# v2164_quad_VCA_0402.net
KiCad netlist of a schematic drawn in EAGLE
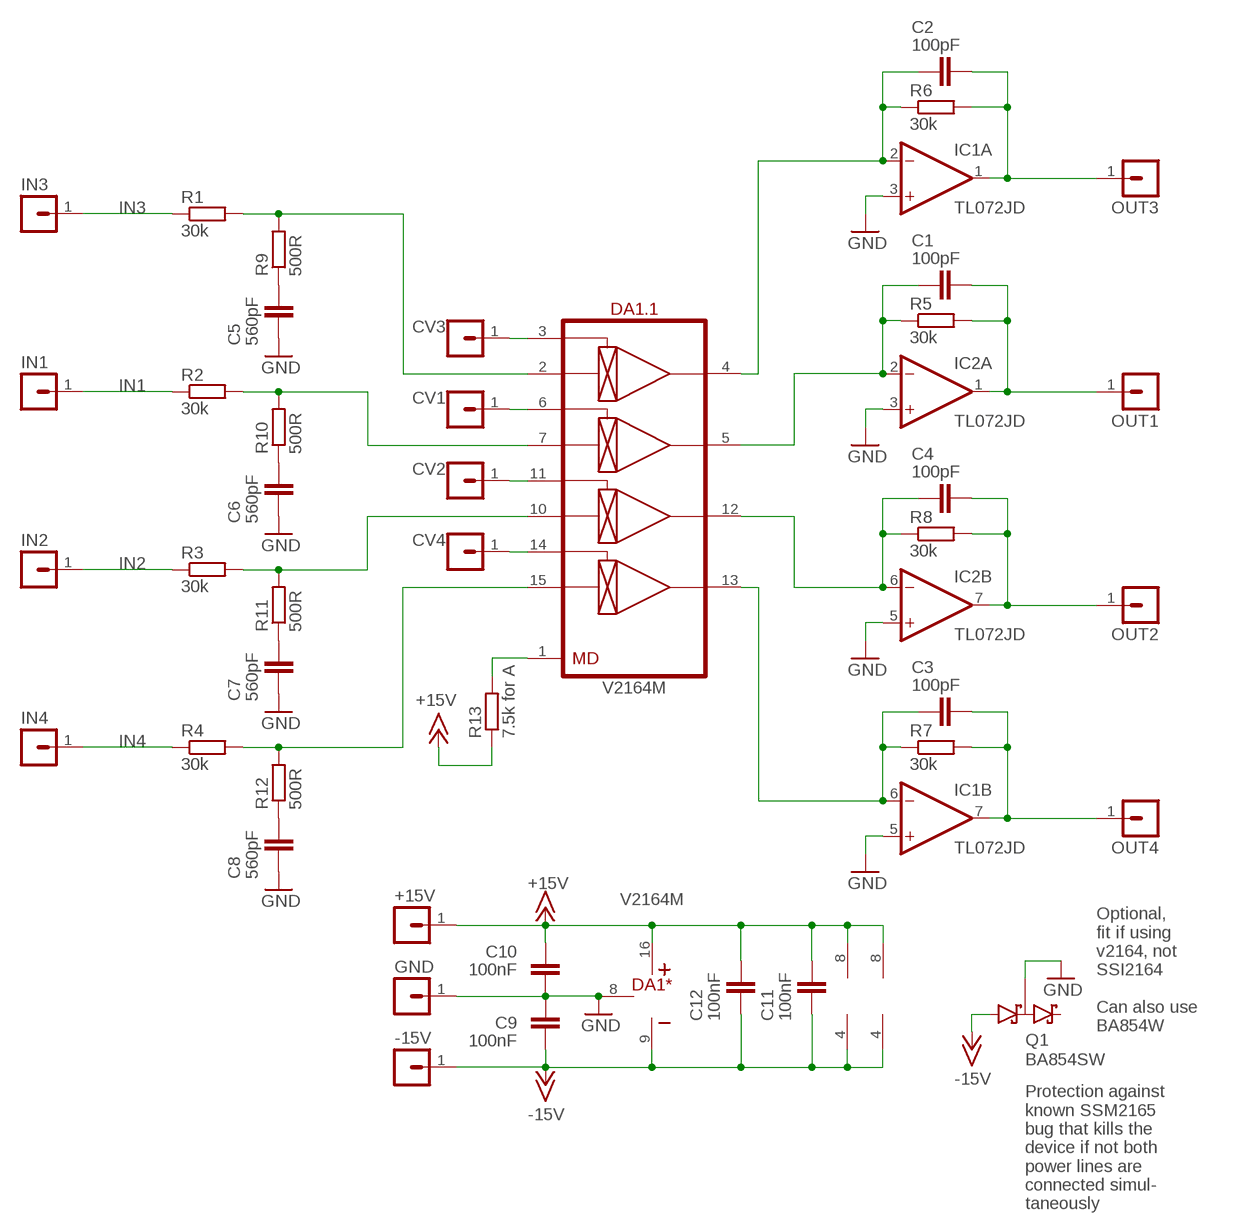
[diagram p0: schematic, sheet 1]

(export (version "E")
  (design (tool "Eeschema 10.0.6"))
  (components
    (comp (ref "+15V")
      (value "MA01-1JN")
      (footprint "eagle-import:MA01N-1J")
      (libsource (lib "eagle-import") (part "MA01-1JN"))
    )
    (comp (ref "-15V")
      (value "MA01-1JN")
      (footprint "eagle-import:MA01N-1J")
      (libsource (lib "eagle-import") (part "MA01-1JN"))
    )
    (comp (ref "C1")
      (value "100pF")
      (footprint "eagle-import:C0402")
      (libsource (lib "eagle-import") (part "C-EUC0402"))
    )
    (comp (ref "C2")
      (value "100pF")
      (footprint "eagle-import:C0402")
      (libsource (lib "eagle-import") (part "C-EUC0402"))
    )
    (comp (ref "C3")
      (value "100pF")
      (footprint "eagle-import:C0402")
      (libsource (lib "eagle-import") (part "C-EUC0402"))
    )
    (comp (ref "C4")
      (value "100pF")
      (footprint "eagle-import:C0402")
      (libsource (lib "eagle-import") (part "C-EUC0402"))
    )
    (comp (ref "C5")
      (value "560pF")
      (footprint "eagle-import:C0603")
      (libsource (lib "eagle-import") (part "C-EUC0603"))
    )
    (comp (ref "C6")
      (value "560pF")
      (footprint "eagle-import:C0603")
      (libsource (lib "eagle-import") (part "C-EUC0603"))
    )
    (comp (ref "C7")
      (value "560pF")
      (footprint "eagle-import:C0603")
      (libsource (lib "eagle-import") (part "C-EUC0603"))
    )
    (comp (ref "C8")
      (value "560pF")
      (footprint "eagle-import:C0603")
      (libsource (lib "eagle-import") (part "C-EUC0603"))
    )
    (comp (ref "C9")
      (value "100nF")
      (footprint "eagle-import:C0402")
      (libsource (lib "eagle-import") (part "C-EUC0402"))
    )
    (comp (ref "C10")
      (value "100nF")
      (footprint "eagle-import:C0402")
      (libsource (lib "eagle-import") (part "C-EUC0402"))
    )
    (comp (ref "C11")
      (value "100nF")
      (footprint "eagle-import:C0402")
      (libsource (lib "eagle-import") (part "C-EUC0402"))
    )
    (comp (ref "C12")
      (value "100nF")
      (footprint "eagle-import:C0402")
      (libsource (lib "eagle-import") (part "C-EUC0402"))
    )
    (comp (ref "CV1")
      (value "MA01-1JN")
      (footprint "eagle-import:MA01N-1J")
      (libsource (lib "eagle-import") (part "MA01-1JN"))
    )
    (comp (ref "CV2")
      (value "MA01-1JN")
      (footprint "eagle-import:MA01N-1J")
      (libsource (lib "eagle-import") (part "MA01-1JN"))
    )
    (comp (ref "CV3")
      (value "MA01-1JN")
      (footprint "eagle-import:MA01N-1J")
      (libsource (lib "eagle-import") (part "MA01-1JN"))
    )
    (comp (ref "CV4")
      (value "MA01-1JN")
      (footprint "eagle-import:MA01N-1J")
      (libsource (lib "eagle-import") (part "MA01-1JN"))
    )
    (comp (ref "DA1")
      (value "V2164M")
      (footprint "eagle-import:SO-16")
      (libsource (lib "eagle-import") (part "V2164M"))
    )
    (comp (ref "GND")
      (value "MA01-1JN")
      (footprint "eagle-import:MA01N-1J")
      (libsource (lib "eagle-import") (part "MA01-1JN"))
    )
    (comp (ref "IC1")
      (value "TL072JD")
      (footprint "eagle-import:SO08J")
      (libsource (lib "eagle-import") (part "TL072JD"))
    )
    (comp (ref "IC2")
      (value "TL072JD")
      (footprint "eagle-import:SO08J")
      (libsource (lib "eagle-import") (part "TL072JD"))
    )
    (comp (ref "IN1")
      (value "MA01-1JN")
      (footprint "eagle-import:MA01N-1J")
      (libsource (lib "eagle-import") (part "MA01-1JN"))
    )
    (comp (ref "IN2")
      (value "MA01-1JN")
      (footprint "eagle-import:MA01N-1J")
      (libsource (lib "eagle-import") (part "MA01-1JN"))
    )
    (comp (ref "IN3")
      (value "MA01-1JN")
      (footprint "eagle-import:MA01N-1J")
      (libsource (lib "eagle-import") (part "MA01-1JN"))
    )
    (comp (ref "IN4")
      (value "MA01-1JN")
      (footprint "eagle-import:MA01N-1J")
      (libsource (lib "eagle-import") (part "MA01-1JN"))
    )
    (comp (ref "OUT1")
      (value "MA01-1JN")
      (footprint "eagle-import:MA01N-1J")
      (libsource (lib "eagle-import") (part "MA01-1JN"))
    )
    (comp (ref "OUT2")
      (value "MA01-1JN")
      (footprint "eagle-import:MA01N-1J")
      (libsource (lib "eagle-import") (part "MA01-1JN"))
    )
    (comp (ref "OUT3")
      (value "MA01-1JN")
      (footprint "eagle-import:MA01N-1J")
      (libsource (lib "eagle-import") (part "MA01-1JN"))
    )
    (comp (ref "OUT4")
      (value "MA01-1JN")
      (footprint "eagle-import:MA01N-1J")
      (libsource (lib "eagle-import") (part "MA01-1JN"))
    )
    (comp (ref "Q1")
      (value "BA854SW")
      (footprint "eagle-import:SOT23-3J")
      (libsource (lib "eagle-import") (part "BA854SW"))
    )
    (comp (ref "R1")
      (value "30k")
      (footprint "eagle-import:R0402")
      (libsource (lib "eagle-import") (part "R-EU_R0402"))
    )
    (comp (ref "R2")
      (value "30k")
      (footprint "eagle-import:R0402")
      (libsource (lib "eagle-import") (part "R-EU_R0402"))
    )
    (comp (ref "R3")
      (value "30k")
      (footprint "eagle-import:R0402")
      (libsource (lib "eagle-import") (part "R-EU_R0402"))
    )
    (comp (ref "R4")
      (value "30k")
      (footprint "eagle-import:R0402")
      (libsource (lib "eagle-import") (part "R-EU_R0402"))
    )
    (comp (ref "R5")
      (value "30k")
      (footprint "eagle-import:R0402")
      (libsource (lib "eagle-import") (part "R-EU_R0402"))
    )
    (comp (ref "R6")
      (value "30k")
      (footprint "eagle-import:R0402")
      (libsource (lib "eagle-import") (part "R-EU_R0402"))
    )
    (comp (ref "R7")
      (value "30k")
      (footprint "eagle-import:R0402")
      (libsource (lib "eagle-import") (part "R-EU_R0402"))
    )
    (comp (ref "R8")
      (value "30k")
      (footprint "eagle-import:R0402")
      (libsource (lib "eagle-import") (part "R-EU_R0402"))
    )
    (comp (ref "R9")
      (value "500R")
      (footprint "eagle-import:R0402")
      (libsource (lib "eagle-import") (part "R-EU_R0402"))
    )
    (comp (ref "R10")
      (value "500R")
      (footprint "eagle-import:R0402")
      (libsource (lib "eagle-import") (part "R-EU_R0402"))
    )
    (comp (ref "R11")
      (value "500R")
      (footprint "eagle-import:R0402")
      (libsource (lib "eagle-import") (part "R-EU_R0402"))
    )
    (comp (ref "R12")
      (value "500R")
      (footprint "eagle-import:R0402")
      (libsource (lib "eagle-import") (part "R-EU_R0402"))
    )
    (comp (ref "R13")
      (value "7.5k for A")
      (footprint "eagle-import:R0402")
      (libsource (lib "eagle-import") (part "R-EU_R0402"))
    )
  )
  (nets
    (net (code "1") (name "+15V") (class "Default")
      (node (ref "+15V") (pin "1") (pinfunction "1_1") (pintype "passive"))
      (node (ref "C10") (pin "2") (pinfunction "2_2") (pintype "passive"))
      (node (ref "C11") (pin "2") (pinfunction "2_2") (pintype "passive"))
      (node (ref "C12") (pin "2") (pinfunction "2_2") (pintype "passive"))
      (node (ref "DA1") (pin "16") (pinfunction "V+_16") (pintype "power_in"))
      (node (ref "IC1") (pin "8") (pinfunction "V+_8") (pintype "power_in"))
      (node (ref "IC2") (pin "8") (pinfunction "V+_8") (pintype "power_in"))
      (node (ref "R13") (pin "1") (pinfunction "1_1") (pintype "passive"))
    )
    (net (code "2") (name "-15V") (class "Default")
      (node (ref "-15V") (pin "1") (pinfunction "1_1") (pintype "passive"))
      (node (ref "C11") (pin "1") (pinfunction "1_1") (pintype "passive"))
      (node (ref "C12") (pin "1") (pinfunction "1_1") (pintype "passive"))
      (node (ref "C9") (pin "1") (pinfunction "1_1") (pintype "passive"))
      (node (ref "DA1") (pin "9") (pinfunction "V-_9") (pintype "power_in"))
      (node (ref "IC1") (pin "4") (pinfunction "V-_4") (pintype "power_in"))
      (node (ref "IC2") (pin "4") (pinfunction "V-_4") (pintype "power_in"))
      (node (ref "Q1") (pin "1") (pinfunction "A1_1") (pintype "passive"))
    )
    (net (code "3") (name "/IN1") (class "Default")
      (node (ref "IN1") (pin "1") (pinfunction "1_1") (pintype "passive"))
      (node (ref "R2") (pin "1") (pinfunction "1_1") (pintype "passive"))
    )
    (net (code "4") (name "/IN2") (class "Default")
      (node (ref "IN2") (pin "1") (pinfunction "1_1") (pintype "passive"))
      (node (ref "R3") (pin "1") (pinfunction "1_1") (pintype "passive"))
    )
    (net (code "5") (name "/IN3") (class "Default")
      (node (ref "IN3") (pin "1") (pinfunction "1_1") (pintype "passive"))
      (node (ref "R1") (pin "1") (pinfunction "1_1") (pintype "passive"))
    )
    (net (code "6") (name "/IN4") (class "Default")
      (node (ref "IN4") (pin "1") (pinfunction "1_1") (pintype "passive"))
      (node (ref "R4") (pin "1") (pinfunction "1_1") (pintype "passive"))
    )
    (net (code "7") (name "GND") (class "Default")
      (node (ref "C10") (pin "1") (pinfunction "1_1") (pintype "passive"))
      (node (ref "C5") (pin "1") (pinfunction "1_1") (pintype "passive"))
      (node (ref "C6") (pin "1") (pinfunction "1_1") (pintype "passive"))
      (node (ref "C7") (pin "1") (pinfunction "1_1") (pintype "passive"))
      (node (ref "C8") (pin "1") (pinfunction "1_1") (pintype "passive"))
      (node (ref "C9") (pin "2") (pinfunction "2_2") (pintype "passive"))
      (node (ref "DA1") (pin "8") (pinfunction "GND_8") (pintype "power_in"))
      (node (ref "GND") (pin "1") (pinfunction "1_1") (pintype "passive"))
      (node (ref "IC1") (pin "3") (pinfunction "+IN_3") (pintype "input"))
      (node (ref "IC1") (pin "5") (pinfunction "+IN_5") (pintype "input"))
      (node (ref "IC2") (pin "3") (pinfunction "+IN_3") (pintype "input"))
      (node (ref "IC2") (pin "5") (pinfunction "+IN_5") (pintype "input"))
      (node (ref "Q1") (pin "3") (pinfunction "K1A2_3") (pintype "passive"))
    )
    (net (code "8") (name "Net-(C5-Pad2)") (class "Default")
      (node (ref "C5") (pin "2") (pinfunction "2_2") (pintype "passive"))
      (node (ref "R9") (pin "1") (pinfunction "1_1") (pintype "passive"))
    )
    (net (code "9") (name "Net-(C6-Pad2)") (class "Default")
      (node (ref "C6") (pin "2") (pinfunction "2_2") (pintype "passive"))
      (node (ref "R10") (pin "1") (pinfunction "1_1") (pintype "passive"))
    )
    (net (code "10") (name "Net-(C7-Pad2)") (class "Default")
      (node (ref "C7") (pin "2") (pinfunction "2_2") (pintype "passive"))
      (node (ref "R11") (pin "1") (pinfunction "1_1") (pintype "passive"))
    )
    (net (code "11") (name "Net-(C8-Pad2)") (class "Default")
      (node (ref "C8") (pin "2") (pinfunction "2_2") (pintype "passive"))
      (node (ref "R12") (pin "1") (pinfunction "1_1") (pintype "passive"))
    )
    (net (code "12") (name "Net-(DA1B-CV1)") (class "Default")
      (node (ref "CV3") (pin "1") (pinfunction "1_1") (pintype "passive"))
      (node (ref "DA1") (pin "3") (pinfunction "CV1_3") (pintype "input"))
    )
    (net (code "13") (name "Net-(DA1B-CV2)") (class "Default")
      (node (ref "CV1") (pin "1") (pinfunction "1_1") (pintype "passive"))
      (node (ref "DA1") (pin "6") (pinfunction "CV2_6") (pintype "input"))
    )
    (net (code "14") (name "Net-(DA1B-CV3)") (class "Default")
      (node (ref "CV2") (pin "1") (pinfunction "1_1") (pintype "passive"))
      (node (ref "DA1") (pin "11") (pinfunction "CV3_11") (pintype "input"))
    )
    (net (code "15") (name "Net-(DA1B-CV4)") (class "Default")
      (node (ref "CV4") (pin "1") (pinfunction "1_1") (pintype "passive"))
      (node (ref "DA1") (pin "14") (pinfunction "CV4_14") (pintype "input"))
    )
    (net (code "16") (name "Net-(DA1B-IN1)") (class "Default")
      (node (ref "DA1") (pin "2") (pinfunction "IN1_2") (pintype "input"))
      (node (ref "R1") (pin "2") (pinfunction "2_2") (pintype "passive"))
      (node (ref "R9") (pin "2") (pinfunction "2_2") (pintype "passive"))
    )
    (net (code "17") (name "Net-(DA1B-IN2)") (class "Default")
      (node (ref "DA1") (pin "7") (pinfunction "IN2_7") (pintype "input"))
      (node (ref "R10") (pin "2") (pinfunction "2_2") (pintype "passive"))
      (node (ref "R2") (pin "2") (pinfunction "2_2") (pintype "passive"))
    )
    (net (code "18") (name "Net-(DA1B-IN3)") (class "Default")
      (node (ref "DA1") (pin "10") (pinfunction "IN3_10") (pintype "input"))
      (node (ref "R11") (pin "2") (pinfunction "2_2") (pintype "passive"))
      (node (ref "R3") (pin "2") (pinfunction "2_2") (pintype "passive"))
    )
    (net (code "19") (name "Net-(DA1B-IN4)") (class "Default")
      (node (ref "DA1") (pin "15") (pinfunction "IN4_15") (pintype "input"))
      (node (ref "R12") (pin "2") (pinfunction "2_2") (pintype "passive"))
      (node (ref "R4") (pin "2") (pinfunction "2_2") (pintype "passive"))
    )
    (net (code "20") (name "Net-(DA1B-MD)") (class "Default")
      (node (ref "DA1") (pin "1") (pinfunction "MD_1") (pintype "output"))
      (node (ref "R13") (pin "2") (pinfunction "2_2") (pintype "passive"))
    )
    (net (code "21") (name "Net-(DA1B-OUT1)") (class "Default")
      (node (ref "C2") (pin "1") (pinfunction "1_1") (pintype "passive"))
      (node (ref "DA1") (pin "4") (pinfunction "OUT1_4") (pintype "output"))
      (node (ref "IC1") (pin "2") (pinfunction "-IN_2") (pintype "input"))
      (node (ref "R6") (pin "1") (pinfunction "1_1") (pintype "passive"))
    )
    (net (code "22") (name "Net-(DA1B-OUT2)") (class "Default")
      (node (ref "C1") (pin "1") (pinfunction "1_1") (pintype "passive"))
      (node (ref "DA1") (pin "5") (pinfunction "OUT2_5") (pintype "output"))
      (node (ref "IC2") (pin "2") (pinfunction "-IN_2") (pintype "input"))
      (node (ref "R5") (pin "1") (pinfunction "1_1") (pintype "passive"))
    )
    (net (code "23") (name "Net-(DA1B-OUT3)") (class "Default")
      (node (ref "C4") (pin "1") (pinfunction "1_1") (pintype "passive"))
      (node (ref "DA1") (pin "12") (pinfunction "OUT3_12") (pintype "output"))
      (node (ref "IC2") (pin "6") (pinfunction "-IN_6") (pintype "input"))
      (node (ref "R8") (pin "1") (pinfunction "1_1") (pintype "passive"))
    )
    (net (code "24") (name "Net-(DA1B-OUT4)") (class "Default")
      (node (ref "C3") (pin "1") (pinfunction "1_1") (pintype "passive"))
      (node (ref "DA1") (pin "13") (pinfunction "OUT4_13") (pintype "output"))
      (node (ref "IC1") (pin "6") (pinfunction "-IN_6") (pintype "input"))
      (node (ref "R7") (pin "1") (pinfunction "1_1") (pintype "passive"))
    )
    (net (code "25") (name "Net-(IC1A-OUT)") (class "Default")
      (node (ref "C2") (pin "2") (pinfunction "2_2") (pintype "passive"))
      (node (ref "IC1") (pin "1") (pinfunction "OUT_1") (pintype "output"))
      (node (ref "OUT3") (pin "1") (pinfunction "1_1") (pintype "passive"))
      (node (ref "R6") (pin "2") (pinfunction "2_2") (pintype "passive"))
    )
    (net (code "26") (name "Net-(IC1B-OUT)") (class "Default")
      (node (ref "C3") (pin "2") (pinfunction "2_2") (pintype "passive"))
      (node (ref "IC1") (pin "7") (pinfunction "OUT_7") (pintype "output"))
      (node (ref "OUT4") (pin "1") (pinfunction "1_1") (pintype "passive"))
      (node (ref "R7") (pin "2") (pinfunction "2_2") (pintype "passive"))
    )
    (net (code "27") (name "Net-(IC2A-OUT)") (class "Default")
      (node (ref "C1") (pin "2") (pinfunction "2_2") (pintype "passive"))
      (node (ref "IC2") (pin "1") (pinfunction "OUT_1") (pintype "output"))
      (node (ref "OUT1") (pin "1") (pinfunction "1_1") (pintype "passive"))
      (node (ref "R5") (pin "2") (pinfunction "2_2") (pintype "passive"))
    )
    (net (code "28") (name "Net-(IC2B-OUT)") (class "Default")
      (node (ref "C4") (pin "2") (pinfunction "2_2") (pintype "passive"))
      (node (ref "IC2") (pin "7") (pinfunction "OUT_7") (pintype "output"))
      (node (ref "OUT2") (pin "1") (pinfunction "1_1") (pintype "passive"))
      (node (ref "R8") (pin "2") (pinfunction "2_2") (pintype "passive"))
    )
    (net (code "29") (name "unconnected-(Q1-K2-Pad2)") (class "Default")
      (node (ref "Q1") (pin "2") (pinfunction "K2_2") (pintype "passive"))
    )
  )
)
